# ready.net
KiCad netlist of a schematic drawn in EAGLE
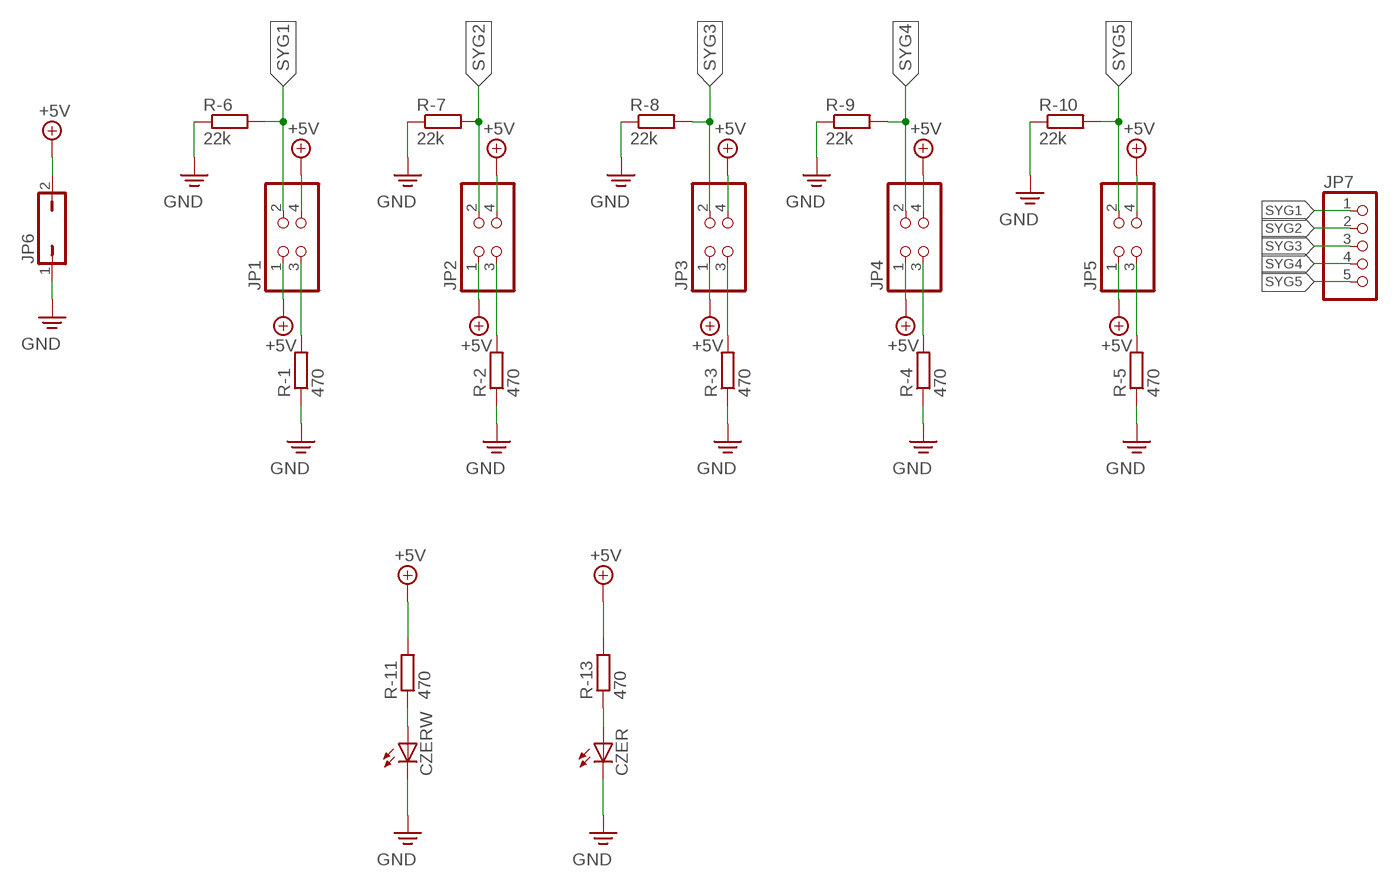
[diagram p0: schematic, sheet 1]

(export (version "E")
  (design (tool "Eeschema 10.0.6"))
  (components
    (comp (ref "CZER")
      (value "LED5MM")
      (footprint "eagle-import:LED5MM")
      (libsource (lib "eagle-import") (part "LED5MM"))
    )
    (comp (ref "CZERW")
      (value "LED5MM")
      (footprint "eagle-import:LED5MM")
      (libsource (lib "eagle-import") (part "LED5MM"))
    )
    (comp (ref "JP1")
      (value "PINHD-2X2")
      (footprint "eagle-import:2X02")
      (libsource (lib "eagle-import") (part "PINHD-2X2"))
    )
    (comp (ref "JP2")
      (value "PINHD-2X2")
      (footprint "eagle-import:2X02")
      (libsource (lib "eagle-import") (part "PINHD-2X2"))
    )
    (comp (ref "JP3")
      (value "PINHD-2X2")
      (footprint "eagle-import:2X02")
      (libsource (lib "eagle-import") (part "PINHD-2X2"))
    )
    (comp (ref "JP4")
      (value "PINHD-2X2")
      (footprint "eagle-import:2X02")
      (libsource (lib "eagle-import") (part "PINHD-2X2"))
    )
    (comp (ref "JP5")
      (value "PINHD-2X2")
      (footprint "eagle-import:2X02")
      (libsource (lib "eagle-import") (part "PINHD-2X2"))
    )
    (comp (ref "JP6")
      (value "JP1Q")
      (footprint "eagle-import:JP1")
      (libsource (lib "eagle-import") (part "JP1Q"))
    )
    (comp (ref "JP7")
      (value "PINHD-1X5")
      (footprint "eagle-import:1X05")
      (libsource (lib "eagle-import") (part "PINHD-1X5"))
    )
    (comp (ref "R-1")
      (value "470")
      (footprint "eagle-import:0204_7")
      (libsource (lib "eagle-import") (part "R-EU_0204/7"))
    )
    (comp (ref "R-2")
      (value "470")
      (footprint "eagle-import:0204_7")
      (libsource (lib "eagle-import") (part "R-EU_0204/7"))
    )
    (comp (ref "R-3")
      (value "470")
      (footprint "eagle-import:0204_7")
      (libsource (lib "eagle-import") (part "R-EU_0204/7"))
    )
    (comp (ref "R-4")
      (value "470")
      (footprint "eagle-import:0204_7")
      (libsource (lib "eagle-import") (part "R-EU_0204/7"))
    )
    (comp (ref "R-5")
      (value "470")
      (footprint "eagle-import:0204_7")
      (libsource (lib "eagle-import") (part "R-EU_0204/7"))
    )
    (comp (ref "R-6")
      (value "22k")
      (footprint "eagle-import:0204_7")
      (libsource (lib "eagle-import") (part "R-EU_0204/7"))
    )
    (comp (ref "R-7")
      (value "22k")
      (footprint "eagle-import:0204_7")
      (libsource (lib "eagle-import") (part "R-EU_0204/7"))
    )
    (comp (ref "R-8")
      (value "22k")
      (footprint "eagle-import:0204_7")
      (libsource (lib "eagle-import") (part "R-EU_0204/7"))
    )
    (comp (ref "R-9")
      (value "22k")
      (footprint "eagle-import:0204_7")
      (libsource (lib "eagle-import") (part "R-EU_0204/7"))
    )
    (comp (ref "R-10")
      (value "22k")
      (footprint "eagle-import:0204_7")
      (libsource (lib "eagle-import") (part "R-EU_0204/7"))
    )
    (comp (ref "R-11")
      (value "470")
      (footprint "eagle-import:0204_7")
      (libsource (lib "eagle-import") (part "R-EU_0204/7"))
    )
    (comp (ref "R-13")
      (value "470")
      (footprint "eagle-import:0204_7")
      (libsource (lib "eagle-import") (part "R-EU_0204/7"))
    )
  )
  (nets
    (net (code "1") (name "+5V") (class "Default")
      (node (ref "JP1") (pin "1") (pinfunction "1_1") (pintype "passive"))
      (node (ref "JP1") (pin "4") (pinfunction "4_4") (pintype "passive"))
      (node (ref "JP2") (pin "1") (pinfunction "1_1") (pintype "passive"))
      (node (ref "JP2") (pin "4") (pinfunction "4_4") (pintype "passive"))
      (node (ref "JP3") (pin "1") (pinfunction "1_1") (pintype "passive"))
      (node (ref "JP3") (pin "4") (pinfunction "4_4") (pintype "passive"))
      (node (ref "JP4") (pin "1") (pinfunction "1_1") (pintype "passive"))
      (node (ref "JP4") (pin "4") (pinfunction "4_4") (pintype "passive"))
      (node (ref "JP5") (pin "1") (pinfunction "1_1") (pintype "passive"))
      (node (ref "JP5") (pin "4") (pinfunction "4_4") (pintype "passive"))
      (node (ref "JP6") (pin "2") (pinfunction "2_2") (pintype "passive"))
      (node (ref "R-11") (pin "2") (pinfunction "2_2") (pintype "passive"))
      (node (ref "R-13") (pin "2") (pinfunction "2_2") (pintype "passive"))
    )
    (net (code "2") (name "GND") (class "Default")
      (node (ref "CZER") (pin "K") (pinfunction "C_K") (pintype "passive"))
      (node (ref "CZERW") (pin "K") (pinfunction "C_K") (pintype "passive"))
      (node (ref "JP6") (pin "1") (pinfunction "1_1") (pintype "passive"))
      (node (ref "R-1") (pin "1") (pinfunction "1_1") (pintype "passive"))
      (node (ref "R-10") (pin "1") (pinfunction "1_1") (pintype "passive"))
      (node (ref "R-2") (pin "1") (pinfunction "1_1") (pintype "passive"))
      (node (ref "R-3") (pin "1") (pinfunction "1_1") (pintype "passive"))
      (node (ref "R-4") (pin "1") (pinfunction "1_1") (pintype "passive"))
      (node (ref "R-5") (pin "1") (pinfunction "1_1") (pintype "passive"))
      (node (ref "R-6") (pin "1") (pinfunction "1_1") (pintype "passive"))
      (node (ref "R-7") (pin "1") (pinfunction "1_1") (pintype "passive"))
      (node (ref "R-8") (pin "1") (pinfunction "1_1") (pintype "passive"))
      (node (ref "R-9") (pin "1") (pinfunction "1_1") (pintype "passive"))
    )
    (net (code "3") (name "Net-(CZER-PadA)") (class "Default")
      (node (ref "CZER") (pin "A") (pinfunction "A_A") (pintype "passive"))
      (node (ref "R-13") (pin "1") (pinfunction "1_1") (pintype "passive"))
    )
    (net (code "4") (name "Net-(CZERW-PadA)") (class "Default")
      (node (ref "CZERW") (pin "A") (pinfunction "A_A") (pintype "passive"))
      (node (ref "R-11") (pin "1") (pinfunction "1_1") (pintype "passive"))
    )
    (net (code "5") (name "Net-(JP1-Pad3)") (class "Default")
      (node (ref "JP1") (pin "3") (pinfunction "3_3") (pintype "passive"))
      (node (ref "R-1") (pin "2") (pinfunction "2_2") (pintype "passive"))
    )
    (net (code "6") (name "Net-(JP2-Pad3)") (class "Default")
      (node (ref "JP2") (pin "3") (pinfunction "3_3") (pintype "passive"))
      (node (ref "R-2") (pin "2") (pinfunction "2_2") (pintype "passive"))
    )
    (net (code "7") (name "Net-(JP3-Pad3)") (class "Default")
      (node (ref "JP3") (pin "3") (pinfunction "3_3") (pintype "passive"))
      (node (ref "R-3") (pin "2") (pinfunction "2_2") (pintype "passive"))
    )
    (net (code "8") (name "Net-(JP4-Pad3)") (class "Default")
      (node (ref "JP4") (pin "3") (pinfunction "3_3") (pintype "passive"))
      (node (ref "R-4") (pin "2") (pinfunction "2_2") (pintype "passive"))
    )
    (net (code "9") (name "Net-(JP5-Pad3)") (class "Default")
      (node (ref "JP5") (pin "3") (pinfunction "3_3") (pintype "passive"))
      (node (ref "R-5") (pin "2") (pinfunction "2_2") (pintype "passive"))
    )
    (net (code "10") (name "SYG1") (class "Default")
      (node (ref "JP1") (pin "2") (pinfunction "2_2") (pintype "passive"))
      (node (ref "JP7") (pin "1") (pinfunction "1_1") (pintype "passive"))
      (node (ref "R-6") (pin "2") (pinfunction "2_2") (pintype "passive"))
    )
    (net (code "11") (name "SYG2") (class "Default")
      (node (ref "JP2") (pin "2") (pinfunction "2_2") (pintype "passive"))
      (node (ref "JP7") (pin "2") (pinfunction "2_2") (pintype "passive"))
      (node (ref "R-7") (pin "2") (pinfunction "2_2") (pintype "passive"))
    )
    (net (code "12") (name "SYG3") (class "Default")
      (node (ref "JP3") (pin "2") (pinfunction "2_2") (pintype "passive"))
      (node (ref "JP7") (pin "3") (pinfunction "3_3") (pintype "passive"))
      (node (ref "R-8") (pin "2") (pinfunction "2_2") (pintype "passive"))
    )
    (net (code "13") (name "SYG4") (class "Default")
      (node (ref "JP4") (pin "2") (pinfunction "2_2") (pintype "passive"))
      (node (ref "JP7") (pin "4") (pinfunction "4_4") (pintype "passive"))
      (node (ref "R-9") (pin "2") (pinfunction "2_2") (pintype "passive"))
    )
    (net (code "14") (name "SYG5") (class "Default")
      (node (ref "JP5") (pin "2") (pinfunction "2_2") (pintype "passive"))
      (node (ref "JP7") (pin "5") (pinfunction "5_5") (pintype "passive"))
      (node (ref "R-10") (pin "2") (pinfunction "2_2") (pintype "passive"))
    )
  )
)
